# mw_am_lpf.net
KiCad netlist of a schematic drawn in EAGLE
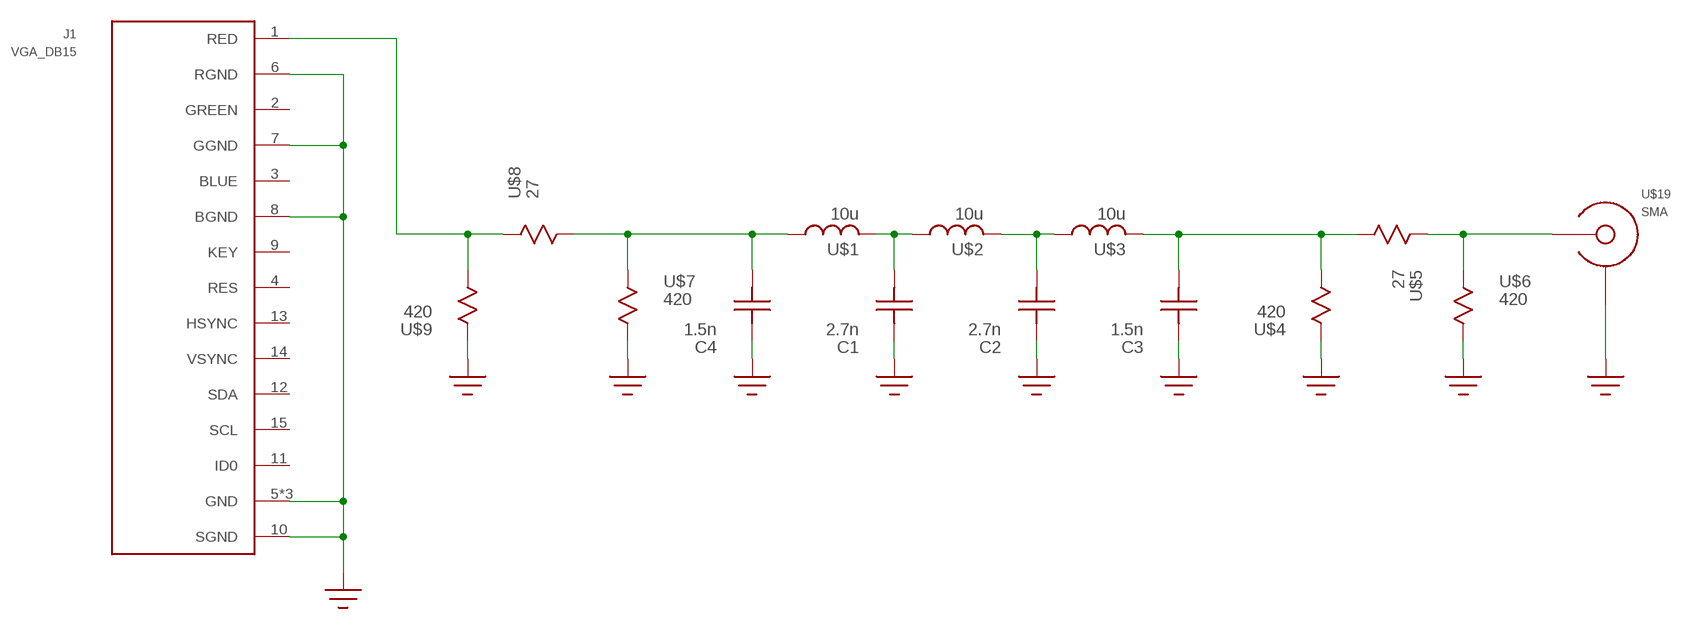
[diagram p0: schematic, sheet 1]

(export (version "E")
  (design (tool "Eeschema 10.0.6"))
  (components
    (comp (ref "C1")
      (value "2.7n")
      (footprint "eagle-import:0805")
      (libsource (lib "eagle-import") (part "C0805"))
    )
    (comp (ref "C2")
      (value "2.7n")
      (footprint "eagle-import:0805")
      (libsource (lib "eagle-import") (part "C0805"))
    )
    (comp (ref "C3")
      (value "1.5n")
      (footprint "eagle-import:0805")
      (libsource (lib "eagle-import") (part "C0805"))
    )
    (comp (ref "C4")
      (value "1.5n")
      (footprint "eagle-import:0805")
      (libsource (lib "eagle-import") (part "C0805"))
    )
    (comp (ref "J1")
      (value "VGA_DB15")
      (footprint "eagle-import:VGA_PCB_MALE")
      (libsource (lib "eagle-import") (part "VGA_DB15"))
    )
    (comp (ref "U$1")
      (value "10u")
      (footprint "eagle-import:L0.4X0.6")
      (libsource (lib "eagle-import") (part "INDUCTORL0.4X0.6"))
    )
    (comp (ref "U$2")
      (value "10u")
      (footprint "eagle-import:L_VERTICAL")
      (libsource (lib "eagle-import") (part "INDUCTOR"))
    )
    (comp (ref "U$3")
      (value "10u")
      (footprint "eagle-import:L0.4X0.6")
      (libsource (lib "eagle-import") (part "INDUCTORL0.4X0.6"))
    )
    (comp (ref "U$4")
      (value "420")
      (footprint "eagle-import:R0805")
      (libsource (lib "eagle-import") (part "R0805"))
    )
    (comp (ref "U$5")
      (value "27")
      (footprint "eagle-import:R0805")
      (libsource (lib "eagle-import") (part "R0805"))
    )
    (comp (ref "U$6")
      (value "420")
      (footprint "eagle-import:R0805")
      (libsource (lib "eagle-import") (part "R0805"))
    )
    (comp (ref "U$7")
      (value "420")
      (footprint "eagle-import:R0805")
      (libsource (lib "eagle-import") (part "R0805"))
    )
    (comp (ref "U$8")
      (value "27")
      (footprint "eagle-import:R0805")
      (libsource (lib "eagle-import") (part "R0805"))
    )
    (comp (ref "U$9")
      (value "420")
      (footprint "eagle-import:R0805")
      (libsource (lib "eagle-import") (part "R0805"))
    )
    (comp (ref "U$19")
      (value "SMA")
      (footprint "eagle-import:EDGE_LAUNCH_RF_CON")
      (libsource (lib "eagle-import") (part "EDGE_LAUNCH_JACK"))
    )
  )
  (nets
    (net (code "1") (name "GND") (class "Default")
      (node (ref "C1") (pin "P$2") (pinfunction "P$2_P$2") (pintype "bidirectional"))
      (node (ref "C2") (pin "P$2") (pinfunction "P$2_P$2") (pintype "bidirectional"))
      (node (ref "C3") (pin "P$2") (pinfunction "P$2_P$2") (pintype "bidirectional"))
      (node (ref "C4") (pin "P$2") (pinfunction "P$2_P$2") (pintype "bidirectional"))
      (node (ref "J1") (pin "10") (pinfunction "SGND_10") (pintype "bidirectional"))
      (node (ref "J1") (pin "5") (pinfunction "GND_5") (pintype "bidirectional"))
      (node (ref "J1") (pin "6") (pinfunction "RGND_6") (pintype "bidirectional"))
      (node (ref "J1") (pin "7") (pinfunction "GGND_7") (pintype "bidirectional"))
      (node (ref "J1") (pin "8") (pinfunction "BGND_8") (pintype "bidirectional"))
      (node (ref "J1") (pin "TAB@1") (pinfunction "GND_TAB@1") (pintype "bidirectional"))
      (node (ref "J1") (pin "TAB@2") (pinfunction "GND_TAB@2") (pintype "bidirectional"))
      (node (ref "U$19") (pin "GND@1") (pinfunction "SHIELD_GND@1") (pintype "bidirectional"))
      (node (ref "U$19") (pin "GND@10") (pinfunction "SHIELD_GND@10") (pintype "bidirectional"))
      (node (ref "U$19") (pin "GND@11") (pinfunction "SHIELD_GND@11") (pintype "bidirectional"))
      (node (ref "U$19") (pin "GND@12") (pinfunction "SHIELD_GND@12") (pintype "bidirectional"))
      (node (ref "U$19") (pin "GND@2") (pinfunction "SHIELD_GND@2") (pintype "bidirectional"))
      (node (ref "U$19") (pin "GND@3") (pinfunction "SHIELD_GND@3") (pintype "bidirectional"))
      (node (ref "U$19") (pin "GND@4") (pinfunction "SHIELD_GND@4") (pintype "bidirectional"))
      (node (ref "U$19") (pin "GND@5") (pinfunction "SHIELD_GND@5") (pintype "bidirectional"))
      (node (ref "U$19") (pin "GND@6") (pinfunction "SHIELD_GND@6") (pintype "bidirectional"))
      (node (ref "U$19") (pin "GND@7") (pinfunction "SHIELD_GND@7") (pintype "bidirectional"))
      (node (ref "U$19") (pin "GND@8") (pinfunction "SHIELD_GND@8") (pintype "bidirectional"))
      (node (ref "U$19") (pin "GND@9") (pinfunction "SHIELD_GND@9") (pintype "bidirectional"))
      (node (ref "U$19") (pin "SHIELD@1") (pinfunction "SHIELD_SHIELD@1") (pintype "bidirectional"))
      (node (ref "U$19") (pin "SHIELD@2") (pinfunction "SHIELD_SHIELD@2") (pintype "bidirectional"))
      (node (ref "U$4") (pin "P$1") (pinfunction "P$3_P$1") (pintype "bidirectional"))
      (node (ref "U$6") (pin "P$2") (pinfunction "P$4_P$2") (pintype "bidirectional"))
      (node (ref "U$7") (pin "P$2") (pinfunction "P$4_P$2") (pintype "bidirectional"))
      (node (ref "U$9") (pin "P$1") (pinfunction "P$3_P$1") (pintype "bidirectional"))
    )
    (net (code "2") (name "Net-(J1-RED)") (class "Default")
      (node (ref "J1") (pin "1") (pinfunction "RED_1") (pintype "bidirectional"))
      (node (ref "U$8") (pin "P$1") (pinfunction "P$3_P$1") (pintype "bidirectional"))
      (node (ref "U$9") (pin "P$2") (pinfunction "P$4_P$2") (pintype "bidirectional"))
    )
    (net (code "3") (name "Net-(U$1-1)") (class "Default")
      (node (ref "C4") (pin "P$1") (pinfunction "P$1_P$1") (pintype "bidirectional"))
      (node (ref "U$1") (pin "P$1") (pinfunction "1_P$1") (pintype "passive"))
      (node (ref "U$7") (pin "P$1") (pinfunction "P$3_P$1") (pintype "bidirectional"))
      (node (ref "U$8") (pin "P$2") (pinfunction "P$4_P$2") (pintype "bidirectional"))
    )
    (net (code "4") (name "Net-(U$1-2)") (class "Default")
      (node (ref "C1") (pin "P$1") (pinfunction "P$1_P$1") (pintype "bidirectional"))
      (node (ref "U$1") (pin "P$2") (pinfunction "2_P$2") (pintype "passive"))
      (node (ref "U$2") (pin "P$1") (pinfunction "1_P$1") (pintype "passive"))
    )
    (net (code "5") (name "Net-(U$2-2)") (class "Default")
      (node (ref "C2") (pin "P$1") (pinfunction "P$1_P$1") (pintype "bidirectional"))
      (node (ref "U$2") (pin "P$2") (pinfunction "2_P$2") (pintype "passive"))
      (node (ref "U$3") (pin "P$1") (pinfunction "1_P$1") (pintype "passive"))
    )
    (net (code "6") (name "Net-(U$3-2)") (class "Default")
      (node (ref "C3") (pin "P$1") (pinfunction "P$1_P$1") (pintype "bidirectional"))
      (node (ref "U$3") (pin "P$2") (pinfunction "2_P$2") (pintype "passive"))
      (node (ref "U$4") (pin "P$2") (pinfunction "P$4_P$2") (pintype "bidirectional"))
      (node (ref "U$5") (pin "P$2") (pinfunction "P$4_P$2") (pintype "bidirectional"))
    )
    (net (code "7") (name "Net-(U$5-P$3)") (class "Default")
      (node (ref "U$19") (pin "CENTER") (pinfunction "CENTER_CENTER") (pintype "bidirectional"))
      (node (ref "U$5") (pin "P$1") (pinfunction "P$3_P$1") (pintype "bidirectional"))
      (node (ref "U$6") (pin "P$1") (pinfunction "P$3_P$1") (pintype "bidirectional"))
    )
    (net (code "8") (name "unconnected-(J1-BLUE-Pad3)") (class "Default")
      (node (ref "J1") (pin "3") (pinfunction "BLUE_3") (pintype "bidirectional"))
    )
    (net (code "9") (name "unconnected-(J1-GREEN-Pad2)") (class "Default")
      (node (ref "J1") (pin "2") (pinfunction "GREEN_2") (pintype "bidirectional"))
    )
    (net (code "10") (name "unconnected-(J1-HSYNC-Pad13)") (class "Default")
      (node (ref "J1") (pin "13") (pinfunction "HSYNC_13") (pintype "bidirectional"))
    )
    (net (code "11") (name "unconnected-(J1-ID0-Pad11)") (class "Default")
      (node (ref "J1") (pin "11") (pinfunction "ID0_11") (pintype "bidirectional"))
    )
    (net (code "12") (name "unconnected-(J1-KEY-Pad9)") (class "Default")
      (node (ref "J1") (pin "9") (pinfunction "KEY_9") (pintype "bidirectional"))
    )
    (net (code "13") (name "unconnected-(J1-RES-Pad4)") (class "Default")
      (node (ref "J1") (pin "4") (pinfunction "RES_4") (pintype "bidirectional"))
    )
    (net (code "14") (name "unconnected-(J1-SCL-Pad15)") (class "Default")
      (node (ref "J1") (pin "15") (pinfunction "SCL_15") (pintype "bidirectional"))
    )
    (net (code "15") (name "unconnected-(J1-SDA-Pad12)") (class "Default")
      (node (ref "J1") (pin "12") (pinfunction "SDA_12") (pintype "bidirectional"))
    )
    (net (code "16") (name "unconnected-(J1-VSYNC-Pad14)") (class "Default")
      (node (ref "J1") (pin "14") (pinfunction "VSYNC_14") (pintype "bidirectional"))
    )
  )
)
